# musIR-tiny-mk-1_0_3.net
KiCad netlist of a schematic drawn in EAGLE
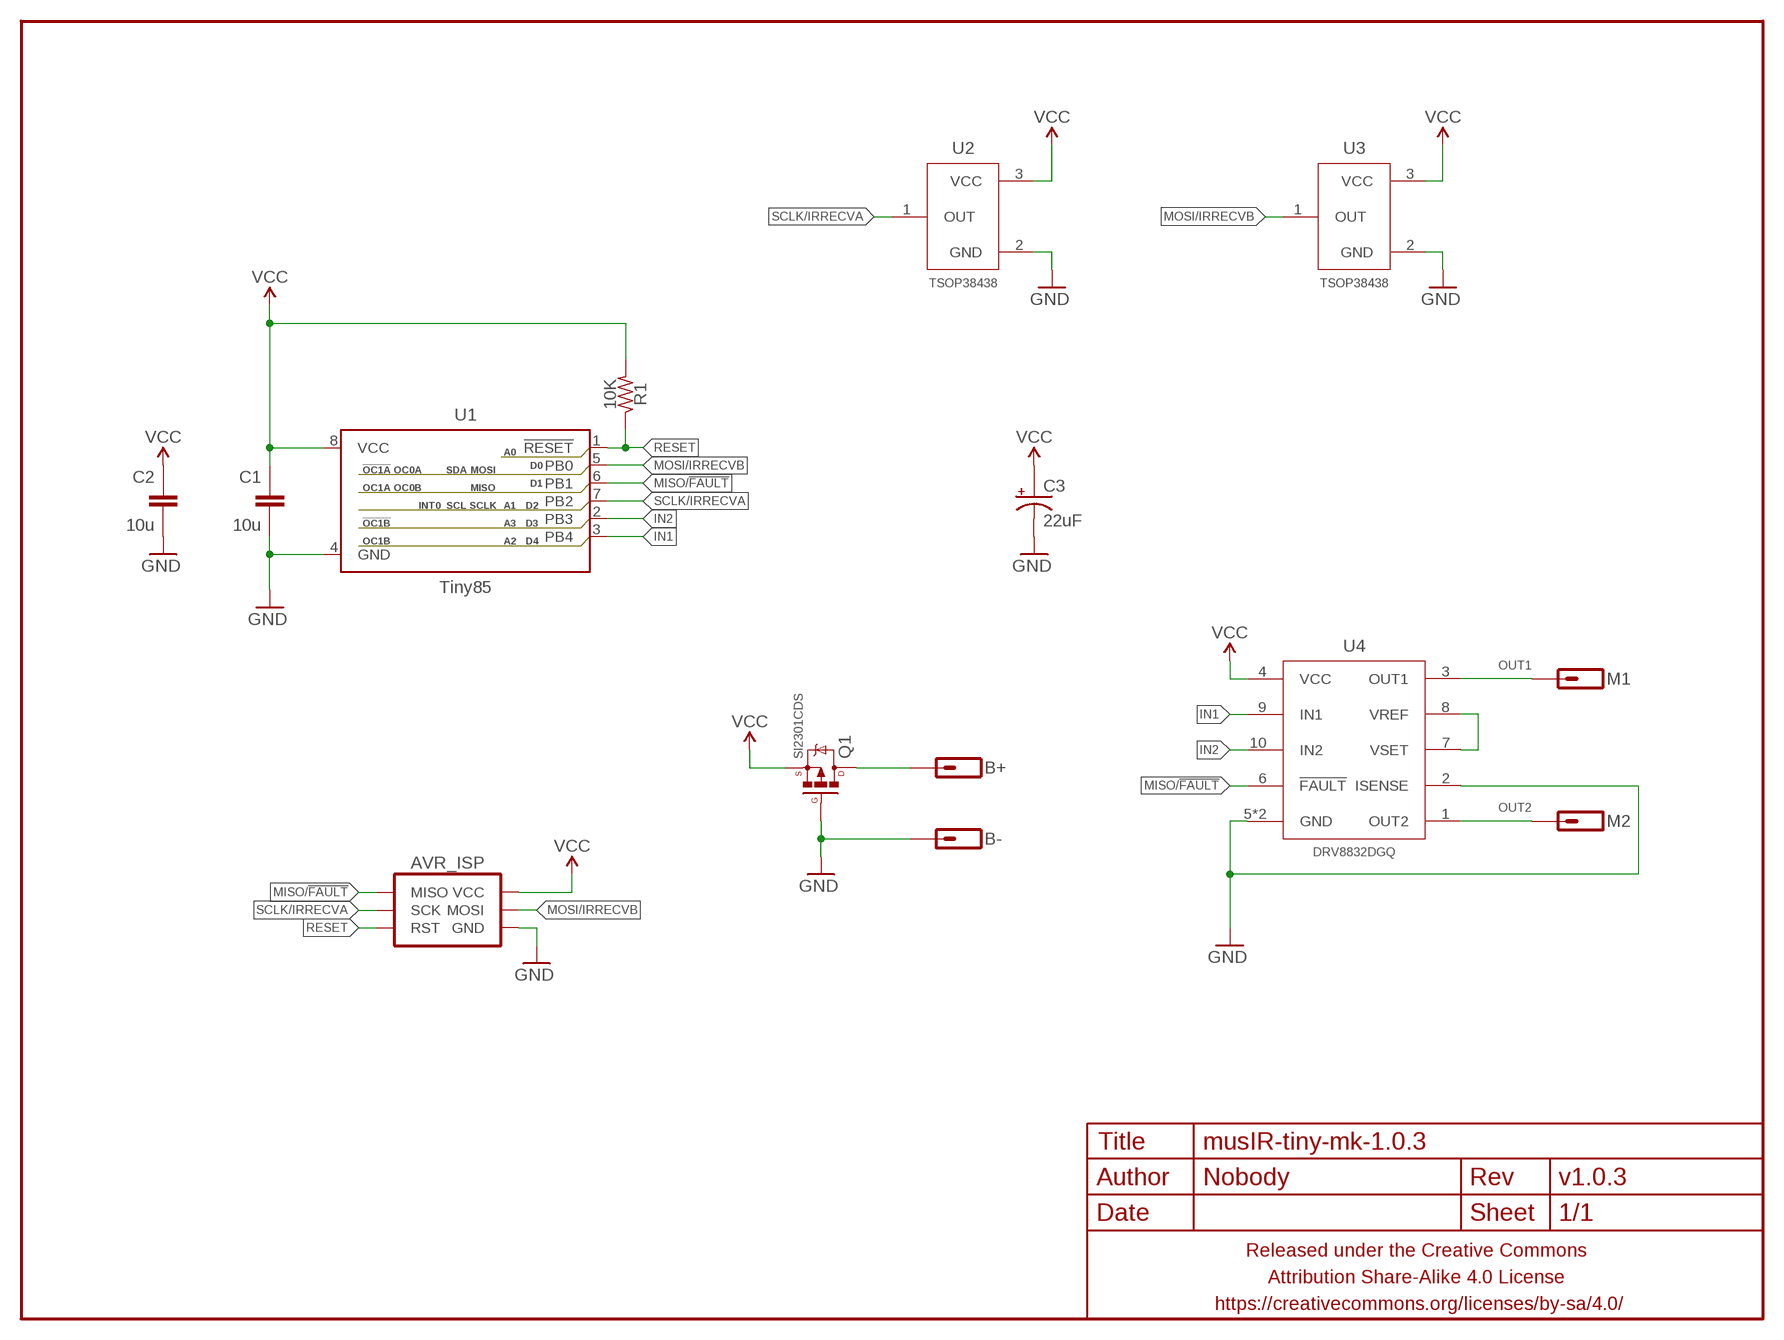
[diagram p0: schematic, sheet 1]

(export (version "E")
  (design (tool "Eeschema 10.0.6"))
  (components
    (comp (ref "AVR_ISP")
      (value "AVR_SPI_PRG_6TESTPOINTS")
      (footprint "eagle-import:2X3_TEST_POINTS")
      (libsource (lib "eagle-import") (part "AVR_SPI_PRG_6TESTPOINTS"))
    )
    (comp (ref "B+")
      (value "M01PTH")
      (footprint "eagle-import:1X01")
      (libsource (lib "eagle-import") (part "M01PTH"))
    )
    (comp (ref "B-")
      (value "M01PTH")
      (footprint "eagle-import:1X01")
      (libsource (lib "eagle-import") (part "M01PTH"))
    )
    (comp (ref "C1")
      (value "10u")
      (footprint "eagle-import:C0805-TIGHTER")
      (libsource (lib "eagle-import") (part "CAPACITOR-CERAMICC0805-TIGHTER"))
    )
    (comp (ref "C2")
      (value "10u")
      (footprint "eagle-import:C0805-TIGHTER")
      (libsource (lib "eagle-import") (part "CAPACITOR-CERAMICC0805-TIGHTER"))
    )
    (comp (ref "C3")
      (value "22uF")
      (footprint "eagle-import:C_6032-28R")
      (libsource (lib "eagle-import") (part "CAPACITOR-POLARIZEDC/6032-28R"))
    )
    (comp (ref "FRAME1")
      (value "FRAME-LETTERNO_PACKAGE")
      (footprint "eagle-import:DUMMY")
      (fields (field (name "VERSION") "v1.0.3") (field (name "DESIGNER") "Nobody"))
      (libsource (lib "eagle-import") (part "FRAME-LETTERNO_PACKAGE"))
    )
    (comp (ref "M1")
      (value "M01PTH")
      (footprint "eagle-import:1X01")
      (libsource (lib "eagle-import") (part "M01PTH"))
    )
    (comp (ref "M2")
      (value "M01PTH")
      (footprint "eagle-import:1X01")
      (libsource (lib "eagle-import") (part "M01PTH"))
    )
    (comp (ref "Q1")
      (value "SI2301CDS")
      (footprint "eagle-import:SOT23")
      (libsource (lib "eagle-import") (part "MOSFET-PCHANNELSOT-23"))
    )
    (comp (ref "R1")
      (value "10K")
      (footprint "eagle-import:R0603-TIGHTER")
      (libsource (lib "eagle-import") (part "RESISTORR0603-TIGHTER"))
    )
    (comp (ref "U1")
      (value "Tiny85")
      (footprint "eagle-import:SO08-EIAJ")
      (libsource (lib "eagle-import") (part "ATTINY45TINY85-20-SOICW"))
    )
    (comp (ref "U2")
      (value "TSOP38438")
      (footprint "eagle-import:TSOP38238")
      (libsource (lib "eagle-import") (part "TSOP382__/4__"))
    )
    (comp (ref "U3")
      (value "TSOP38438")
      (footprint "eagle-import:TSOP38238")
      (libsource (lib "eagle-import") (part "TSOP382__/4__"))
    )
    (comp (ref "U4")
      (value "DRV8832DGQ")
      (footprint "eagle-import:MSOP-10-PAD")
      (libsource (lib "eagle-import") (part "DRV8832DGQ"))
    )
  )
  (nets
    (net (code "1") (name "/MISO{slash}~{FAULT}") (class "Default")
      (node (ref "AVR_ISP") (pin "1") (pinfunction "MISO_1") (pintype "passive"))
      (node (ref "U1") (pin "6") (pinfunction "PB1_6") (pintype "bidirectional"))
      (node (ref "U4") (pin "6") (pinfunction "~{FAULT}_6") (pintype "bidirectional"))
    )
    (net (code "2") (name "/OUT1") (class "Default")
      (node (ref "M1") (pin "1") (pinfunction "1_1") (pintype "passive"))
      (node (ref "U4") (pin "3") (pinfunction "OUT1_3") (pintype "bidirectional"))
    )
    (net (code "3") (name "/OUT2") (class "Default")
      (node (ref "M2") (pin "1") (pinfunction "1_1") (pintype "passive"))
      (node (ref "U4") (pin "1") (pinfunction "OUT2_1") (pintype "bidirectional"))
    )
    (net (code "4") (name "GND") (class "Default")
      (node (ref "AVR_ISP") (pin "6") (pinfunction "GND_6") (pintype "passive"))
      (node (ref "B-") (pin "1") (pinfunction "1_1") (pintype "passive"))
      (node (ref "C1") (pin "2") (pinfunction "2_2") (pintype "passive"))
      (node (ref "C2") (pin "2") (pinfunction "2_2") (pintype "passive"))
      (node (ref "C3") (pin "-") (pinfunction "-_-") (pintype "passive"))
      (node (ref "Q1") (pin "1") (pinfunction "G_1") (pintype "passive"))
      (node (ref "U1") (pin "4") (pinfunction "GND_4") (pintype "bidirectional"))
      (node (ref "U2") (pin "2") (pinfunction "GND_2") (pintype "bidirectional"))
      (node (ref "U3") (pin "2") (pinfunction "GND_2") (pintype "bidirectional"))
      (node (ref "U4") (pin "2") (pinfunction "ISENSE_2") (pintype "bidirectional"))
      (node (ref "U4") (pin "5") (pinfunction "GND_5") (pintype "bidirectional"))
      (node (ref "U4") (pin "PAD") (pinfunction "GND_PAD") (pintype "bidirectional"))
    )
    (net (code "5") (name "IN1") (class "Default")
      (node (ref "U1") (pin "3") (pinfunction "PB4_3") (pintype "bidirectional"))
      (node (ref "U4") (pin "9") (pinfunction "IN1_9") (pintype "bidirectional"))
    )
    (net (code "6") (name "IN2") (class "Default")
      (node (ref "U1") (pin "2") (pinfunction "PB3_2") (pintype "bidirectional"))
      (node (ref "U4") (pin "10") (pinfunction "IN2_10") (pintype "bidirectional"))
    )
    (net (code "7") (name "MOSI{slash}IRRECVB") (class "Default")
      (node (ref "AVR_ISP") (pin "4") (pinfunction "MOSI_4") (pintype "passive"))
      (node (ref "U1") (pin "5") (pinfunction "PB0_5") (pintype "bidirectional"))
      (node (ref "U3") (pin "1") (pinfunction "OUT_1") (pintype "bidirectional"))
    )
    (net (code "8") (name "Net-(Q1-D)") (class "Default")
      (node (ref "B+") (pin "1") (pinfunction "1_1") (pintype "passive"))
      (node (ref "Q1") (pin "3") (pinfunction "D_3") (pintype "passive"))
    )
    (net (code "9") (name "Net-(U4-VREF)") (class "Default")
      (node (ref "U4") (pin "7") (pinfunction "VSET_7") (pintype "bidirectional"))
      (node (ref "U4") (pin "8") (pinfunction "VREF_8") (pintype "bidirectional"))
    )
    (net (code "10") (name "RESET") (class "Default")
      (node (ref "AVR_ISP") (pin "5") (pinfunction "RST_5") (pintype "passive"))
      (node (ref "R1") (pin "1") (pinfunction "1_1") (pintype "passive"))
      (node (ref "U1") (pin "1") (pinfunction "~{RESET}_1") (pintype "bidirectional"))
    )
    (net (code "11") (name "SCLK{slash}IRRECVA") (class "Default")
      (node (ref "AVR_ISP") (pin "3") (pinfunction "SCK_3") (pintype "passive"))
      (node (ref "U1") (pin "7") (pinfunction "PB2_7") (pintype "bidirectional"))
      (node (ref "U2") (pin "1") (pinfunction "OUT_1") (pintype "bidirectional"))
    )
    (net (code "12") (name "VCC") (class "Default")
      (node (ref "AVR_ISP") (pin "2") (pinfunction "VCC_2") (pintype "passive"))
      (node (ref "C1") (pin "1") (pinfunction "1_1") (pintype "passive"))
      (node (ref "C2") (pin "1") (pinfunction "1_1") (pintype "passive"))
      (node (ref "C3") (pin "+") (pinfunction "+_+") (pintype "passive"))
      (node (ref "Q1") (pin "2") (pinfunction "S_2") (pintype "passive"))
      (node (ref "R1") (pin "2") (pinfunction "2_2") (pintype "passive"))
      (node (ref "U1") (pin "8") (pinfunction "VCC_8") (pintype "bidirectional"))
      (node (ref "U2") (pin "3") (pinfunction "VCC_3") (pintype "bidirectional"))
      (node (ref "U3") (pin "3") (pinfunction "VCC_3") (pintype "bidirectional"))
      (node (ref "U4") (pin "4") (pinfunction "VCC_4") (pintype "bidirectional"))
    )
  )
)
